# AnalogValuePreparation.net
KiCad netlist of a schematic drawn in Altium Designer
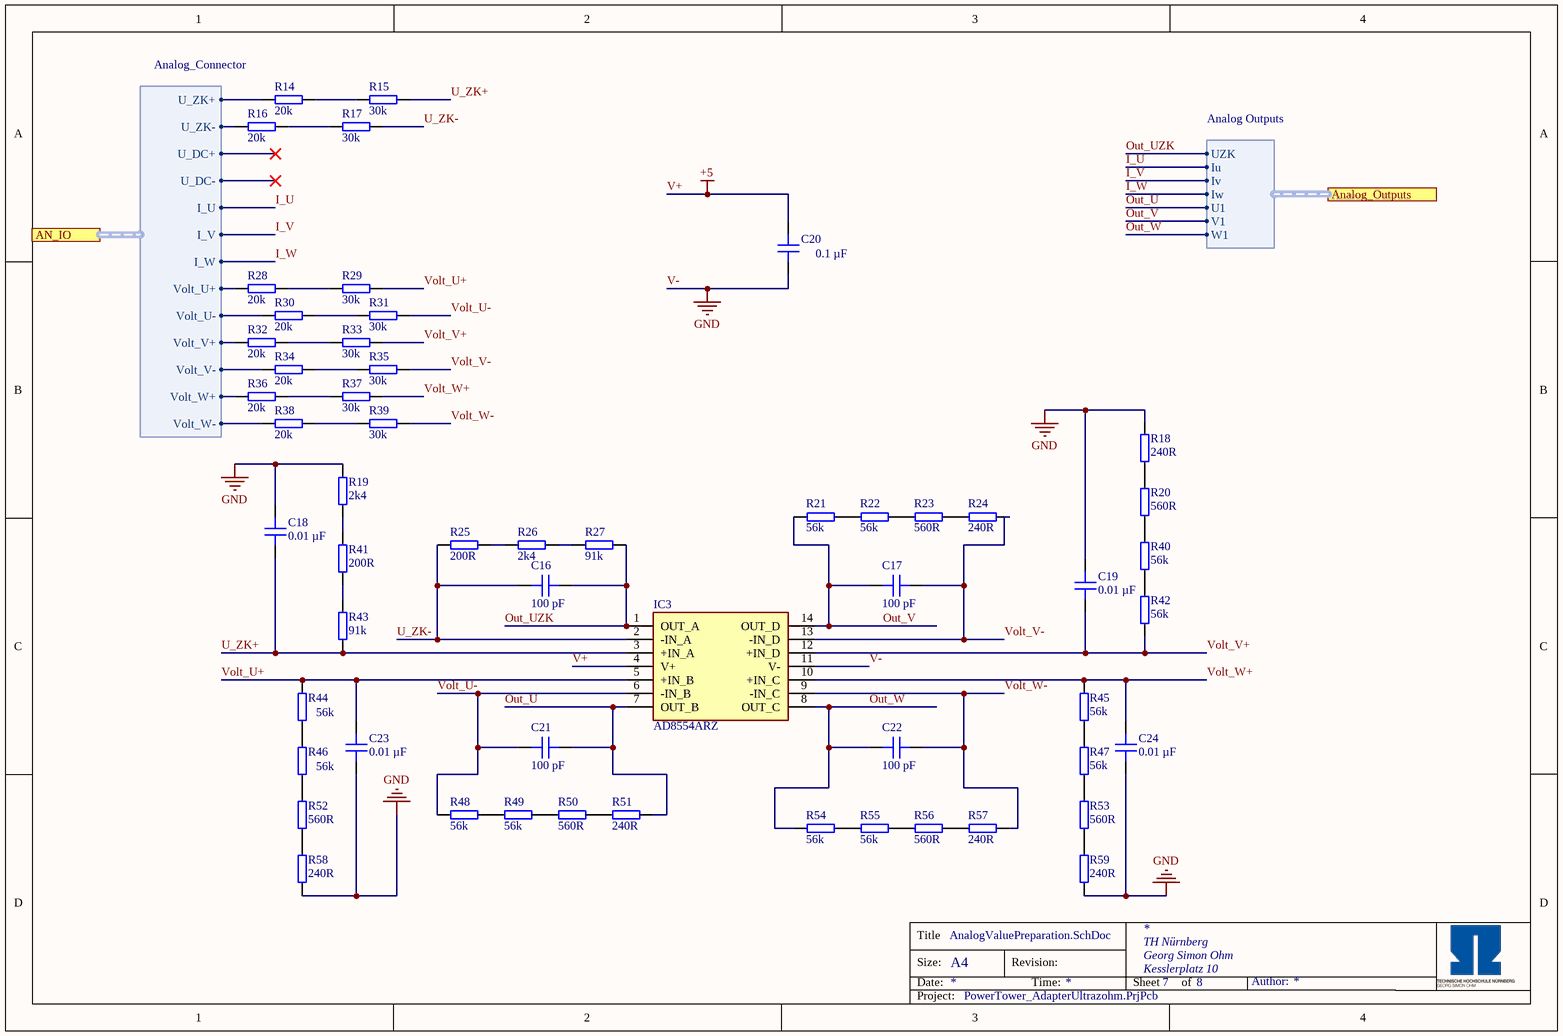
[diagram p0: AnalogValuePreparation.SchDoc]

(export (version "E")
  (design (tool "Eeschema 10.0.6"))
  (components
    (comp (ref "C16")
      (value "100 pF")
      (footprint "C_0603")
      (description "Capacitor 0603, 50 VDC, 100 pF, C0G")
      (fields
        (field (name "MANUFACTURER PART NUMBER") "885012006057")
        (field (name "MANUFACTURER") "Wuerth Elektronik")
        (field (name "CREATED FROM") "MGremer")
      )
      (libsource (lib "user") (part "Capacitor"))
    )
    (comp (ref "C17")
      (value "100 pF")
      (footprint "C_0603")
      (description "Capacitor 0603, 50 VDC, 100 pF, C0G")
      (fields
        (field (name "MANUFACTURER PART NUMBER") "885012006057")
        (field (name "MANUFACTURER") "Wuerth Elektronik")
        (field (name "CREATED FROM") "MGremer")
      )
      (libsource (lib "user") (part "Capacitor"))
    )
    (comp (ref "C18")
      (value "0.01 µF")
      (footprint "C_0603")
      (description "Capacitor 0603, 50 VDC, 0.01 µF, X7R")
      (fields
        (field (name "MANUFACTURER PART NUMBER") "GCJ188R71H103KA01D")
        (field (name "MANUFACTURER") "muRata")
        (field (name "CREATED FROM") "MGremer")
      )
      (libsource (lib "user") (part "Capacitor"))
    )
    (comp (ref "C19")
      (value "0.01 µF")
      (footprint "C_0603")
      (description "Capacitor 0603, 50 VDC, 0.01 µF, X7R")
      (fields
        (field (name "MANUFACTURER PART NUMBER") "GCJ188R71H103KA01D")
        (field (name "MANUFACTURER") "muRata")
        (field (name "CREATED FROM") "MGremer")
      )
      (libsource (lib "user") (part "Capacitor"))
    )
    (comp (ref "C20")
      (value "0.1 µF")
      (footprint "C_0603")
      (description "Capacitor 0603, 50 VDC, 0.1 µF, X7R")
      (fields
        (field (name "MANUFACTURER PART NUMBER") "C0603X104K5RAC7411")
        (field (name "MANUFACTURER") "KEMET")
        (field (name "CREATED FROM") "MGremer")
      )
      (libsource (lib "user") (part "Capacitor"))
    )
    (comp (ref "C21")
      (value "100 pF")
      (footprint "C_0603")
      (description "Capacitor 0603, 50 VDC, 100 pF, C0G")
      (fields
        (field (name "MANUFACTURER PART NUMBER") "885012006057")
        (field (name "MANUFACTURER") "Wuerth Elektronik")
        (field (name "CREATED FROM") "MGremer")
      )
      (libsource (lib "user") (part "Capacitor"))
    )
    (comp (ref "C22")
      (value "100 pF")
      (footprint "C_0603")
      (description "Capacitor 0603, 50 VDC, 100 pF, C0G")
      (fields
        (field (name "MANUFACTURER PART NUMBER") "885012006057")
        (field (name "MANUFACTURER") "Wuerth Elektronik")
        (field (name "CREATED FROM") "MGremer")
      )
      (libsource (lib "user") (part "Capacitor"))
    )
    (comp (ref "C23")
      (value "0.01 µF")
      (footprint "C_0603")
      (description "Capacitor 0603, 50 VDC, 0.01 µF, X7R")
      (fields
        (field (name "MANUFACTURER PART NUMBER") "GCJ188R71H103KA01D")
        (field (name "MANUFACTURER") "muRata")
        (field (name "CREATED FROM") "MGremer")
      )
      (libsource (lib "user") (part "Capacitor"))
    )
    (comp (ref "C24")
      (value "0.01 µF")
      (footprint "C_0603")
      (description "Capacitor 0603, 50 VDC, 0.01 µF, X7R")
      (fields
        (field (name "MANUFACTURER PART NUMBER") "GCJ188R71H103KA01D")
        (field (name "MANUFACTURER") "muRata")
        (field (name "CREATED FROM") "MGremer")
      )
      (libsource (lib "user") (part "Capacitor"))
    )
    (comp (ref "IC3")
      (value "AD8554ARZ")
      (footprint "SOIC127P600X175-14N")
      (description "Differential Amplifier, 3V 1.5MHz, 145dB")
      (fields (field (name "MANUFACTURER") "Analog Devices") (field (name "CREATED FROM") "TWilfling"))
      (libsource (lib "user") (part "AD8554ARZ"))
    )
    (comp (ref "R14")
      (value "20k")
      (footprint "RES 0603_1608")
      (description "SMD resistor E24 series")
      (fields
        (field (name "MANUFACTURER PART NUMBER") "RK73B1JTTD203J")
        (field (name "MANUFACTURER") "KOA Speer")
        (field (name "CREATED FROM") "MGremer")
      )
      (libsource (lib "user") (part "Resistor"))
    )
    (comp (ref "R15")
      (value "30k")
      (footprint "RES 0603_1608")
      (description "SMD resistor E24 series")
      (fields
        (field (name "MANUFACTURER PART NUMBER") "RK73B1JTTD303J")
        (field (name "MANUFACTURER") "KOA Speer")
        (field (name "CREATED FROM") "MGremer")
      )
      (libsource (lib "user") (part "Resistor"))
    )
    (comp (ref "R16")
      (value "20k")
      (footprint "RES 0603_1608")
      (description "SMD resistor E24 series")
      (fields
        (field (name "MANUFACTURER PART NUMBER") "RK73B1JTTD203J")
        (field (name "MANUFACTURER") "KOA Speer")
        (field (name "CREATED FROM") "MGremer")
      )
      (libsource (lib "user") (part "Resistor"))
    )
    (comp (ref "R17")
      (value "30k")
      (footprint "RES 0603_1608")
      (description "SMD resistor E24 series")
      (fields
        (field (name "MANUFACTURER PART NUMBER") "RK73B1JTTD303J")
        (field (name "MANUFACTURER") "KOA Speer")
        (field (name "CREATED FROM") "MGremer")
      )
      (libsource (lib "user") (part "Resistor"))
    )
    (comp (ref "R18")
      (value "240R")
      (footprint "RES 0603_1608")
      (description "SMD resistor E24 series")
      (fields
        (field (name "MANUFACTURER PART NUMBER") "RK73B1JTTDD241J")
        (field (name "MANUFACTURER") "KOA Speer")
        (field (name "CREATED FROM") "MGremer")
      )
      (libsource (lib "user") (part "Resistor"))
    )
    (comp (ref "R19")
      (value "2k4")
      (footprint "RES 0603_1608")
      (description "SMD resistor E24 series")
      (fields
        (field (name "MANUFACTURER PART NUMBER") "RK73B1JTTDD242J")
        (field (name "MANUFACTURER") "KOA Speer")
        (field (name "CREATED FROM") "MGremer")
      )
      (libsource (lib "user") (part "Resistor"))
    )
    (comp (ref "R20")
      (value "560R")
      (footprint "RES 0603_1608")
      (description "SMD resistor E24 series")
      (fields
        (field (name "MANUFACTURER PART NUMBER") "RK73B1JTTD561J")
        (field (name "MANUFACTURER") "KOA Speer")
        (field (name "CREATED FROM") "MGremer")
      )
      (libsource (lib "user") (part "Resistor"))
    )
    (comp (ref "R21")
      (value "56k")
      (footprint "RES 0603_1608")
      (description "SMD resistor E24 series")
      (fields
        (field (name "MANUFACTURER PART NUMBER") "RK73B1JTTDD563J")
        (field (name "MANUFACTURER") "KOA Speer")
        (field (name "CREATED FROM") "MGremer")
      )
      (libsource (lib "user") (part "Resistor"))
    )
    (comp (ref "R22")
      (value "56k")
      (footprint "RES 0603_1608")
      (description "SMD resistor E24 series")
      (fields
        (field (name "MANUFACTURER PART NUMBER") "RK73B1JTTDD563J")
        (field (name "MANUFACTURER") "KOA Speer")
        (field (name "CREATED FROM") "MGremer")
      )
      (libsource (lib "user") (part "Resistor"))
    )
    (comp (ref "R23")
      (value "560R")
      (footprint "RES 0603_1608")
      (description "SMD resistor E24 series")
      (fields
        (field (name "MANUFACTURER PART NUMBER") "RK73B1JTTD561J")
        (field (name "MANUFACTURER") "KOA Speer")
        (field (name "CREATED FROM") "MGremer")
      )
      (libsource (lib "user") (part "Resistor"))
    )
    (comp (ref "R24")
      (value "240R")
      (footprint "RES 0603_1608")
      (description "SMD resistor E24 series")
      (fields
        (field (name "MANUFACTURER PART NUMBER") "RK73B1JTTDD241J")
        (field (name "MANUFACTURER") "KOA Speer")
        (field (name "CREATED FROM") "MGremer")
      )
      (libsource (lib "user") (part "Resistor"))
    )
    (comp (ref "R25")
      (value "200R")
      (footprint "RES 0603_1608")
      (description "SMD resistor E24 series")
      (fields
        (field (name "MANUFACTURER PART NUMBER") "RK73B1JTTD201J")
        (field (name "MANUFACTURER") "KOA Speer")
        (field (name "CREATED FROM") "MGremer")
      )
      (libsource (lib "user") (part "Resistor"))
    )
    (comp (ref "R26")
      (value "2k4")
      (footprint "RES 0603_1608")
      (description "SMD resistor E24 series")
      (fields
        (field (name "MANUFACTURER PART NUMBER") "RK73B1JTTDD242J")
        (field (name "MANUFACTURER") "KOA Speer")
        (field (name "CREATED FROM") "MGremer")
      )
      (libsource (lib "user") (part "Resistor"))
    )
    (comp (ref "R27")
      (value "91k")
      (footprint "RES 0603_1608")
      (description "SMD resistor E24 series")
      (fields
        (field (name "MANUFACTURER PART NUMBER") "RK73B1JTTDD913J")
        (field (name "MANUFACTURER") "KOA Speer")
        (field (name "CREATED FROM") "MGremer")
      )
      (libsource (lib "user") (part "Resistor"))
    )
    (comp (ref "R28")
      (value "20k")
      (footprint "RES 0603_1608")
      (description "SMD resistor E24 series")
      (fields
        (field (name "MANUFACTURER PART NUMBER") "RK73B1JTTD203J")
        (field (name "MANUFACTURER") "KOA Speer")
        (field (name "CREATED FROM") "MGremer")
      )
      (libsource (lib "user") (part "Resistor"))
    )
    (comp (ref "R29")
      (value "30k")
      (footprint "RES 0603_1608")
      (description "SMD resistor E24 series")
      (fields
        (field (name "MANUFACTURER PART NUMBER") "RK73B1JTTD303J")
        (field (name "MANUFACTURER") "KOA Speer")
        (field (name "CREATED FROM") "MGremer")
      )
      (libsource (lib "user") (part "Resistor"))
    )
    (comp (ref "R30")
      (value "20k")
      (footprint "RES 0603_1608")
      (description "SMD resistor E24 series")
      (fields
        (field (name "MANUFACTURER PART NUMBER") "RK73B1JTTD203J")
        (field (name "MANUFACTURER") "KOA Speer")
        (field (name "CREATED FROM") "MGremer")
      )
      (libsource (lib "user") (part "Resistor"))
    )
    (comp (ref "R31")
      (value "30k")
      (footprint "RES 0603_1608")
      (description "SMD resistor E24 series")
      (fields
        (field (name "MANUFACTURER PART NUMBER") "RK73B1JTTD303J")
        (field (name "MANUFACTURER") "KOA Speer")
        (field (name "CREATED FROM") "MGremer")
      )
      (libsource (lib "user") (part "Resistor"))
    )
    (comp (ref "R32")
      (value "20k")
      (footprint "RES 0603_1608")
      (description "SMD resistor E24 series")
      (fields
        (field (name "MANUFACTURER PART NUMBER") "RK73B1JTTD203J")
        (field (name "MANUFACTURER") "KOA Speer")
        (field (name "CREATED FROM") "MGremer")
      )
      (libsource (lib "user") (part "Resistor"))
    )
    (comp (ref "R33")
      (value "30k")
      (footprint "RES 0603_1608")
      (description "SMD resistor E24 series")
      (fields
        (field (name "MANUFACTURER PART NUMBER") "RK73B1JTTD303J")
        (field (name "MANUFACTURER") "KOA Speer")
        (field (name "CREATED FROM") "MGremer")
      )
      (libsource (lib "user") (part "Resistor"))
    )
    (comp (ref "R34")
      (value "20k")
      (footprint "RES 0603_1608")
      (description "SMD resistor E24 series")
      (fields
        (field (name "MANUFACTURER PART NUMBER") "RK73B1JTTD203J")
        (field (name "MANUFACTURER") "KOA Speer")
        (field (name "CREATED FROM") "MGremer")
      )
      (libsource (lib "user") (part "Resistor"))
    )
    (comp (ref "R35")
      (value "30k")
      (footprint "RES 0603_1608")
      (description "SMD resistor E24 series")
      (fields
        (field (name "MANUFACTURER PART NUMBER") "RK73B1JTTD303J")
        (field (name "MANUFACTURER") "KOA Speer")
        (field (name "CREATED FROM") "MGremer")
      )
      (libsource (lib "user") (part "Resistor"))
    )
    (comp (ref "R36")
      (value "20k")
      (footprint "RES 0603_1608")
      (description "SMD resistor E24 series")
      (fields
        (field (name "MANUFACTURER PART NUMBER") "RK73B1JTTD203J")
        (field (name "MANUFACTURER") "KOA Speer")
        (field (name "CREATED FROM") "MGremer")
      )
      (libsource (lib "user") (part "Resistor"))
    )
    (comp (ref "R37")
      (value "30k")
      (footprint "RES 0603_1608")
      (description "SMD resistor E24 series")
      (fields
        (field (name "MANUFACTURER PART NUMBER") "RK73B1JTTD303J")
        (field (name "MANUFACTURER") "KOA Speer")
        (field (name "CREATED FROM") "MGremer")
      )
      (libsource (lib "user") (part "Resistor"))
    )
    (comp (ref "R38")
      (value "20k")
      (footprint "RES 0603_1608")
      (description "SMD resistor E24 series")
      (fields
        (field (name "MANUFACTURER PART NUMBER") "RK73B1JTTD203J")
        (field (name "MANUFACTURER") "KOA Speer")
        (field (name "CREATED FROM") "MGremer")
      )
      (libsource (lib "user") (part "Resistor"))
    )
    (comp (ref "R39")
      (value "30k")
      (footprint "RES 0603_1608")
      (description "SMD resistor E24 series")
      (fields
        (field (name "MANUFACTURER PART NUMBER") "RK73B1JTTD303J")
        (field (name "MANUFACTURER") "KOA Speer")
        (field (name "CREATED FROM") "MGremer")
      )
      (libsource (lib "user") (part "Resistor"))
    )
    (comp (ref "R40")
      (value "56k")
      (footprint "RES 0603_1608")
      (description "SMD resistor E24 series")
      (fields
        (field (name "MANUFACTURER PART NUMBER") "RK73B1JTTDD563J")
        (field (name "MANUFACTURER") "KOA Speer")
        (field (name "CREATED FROM") "MGremer")
      )
      (libsource (lib "user") (part "Resistor"))
    )
    (comp (ref "R41")
      (value "200R")
      (footprint "RES 0603_1608")
      (description "SMD resistor E24 series")
      (fields
        (field (name "MANUFACTURER PART NUMBER") "RK73B1JTTD201J")
        (field (name "MANUFACTURER") "KOA Speer")
        (field (name "CREATED FROM") "MGremer")
      )
      (libsource (lib "user") (part "Resistor"))
    )
    (comp (ref "R42")
      (value "56k")
      (footprint "RES 0603_1608")
      (description "SMD resistor E24 series")
      (fields
        (field (name "MANUFACTURER PART NUMBER") "RK73B1JTTDD563J")
        (field (name "MANUFACTURER") "KOA Speer")
        (field (name "CREATED FROM") "MGremer")
      )
      (libsource (lib "user") (part "Resistor"))
    )
    (comp (ref "R43")
      (value "91k")
      (footprint "RES 0603_1608")
      (description "SMD resistor E24 series")
      (fields
        (field (name "MANUFACTURER PART NUMBER") "RK73B1JTTDD913J")
        (field (name "MANUFACTURER") "KOA Speer")
        (field (name "CREATED FROM") "MGremer")
      )
      (libsource (lib "user") (part "Resistor"))
    )
    (comp (ref "R44")
      (value "56k")
      (footprint "RES 0603_1608")
      (description "SMD resistor E24 series")
      (fields
        (field (name "MANUFACTURER PART NUMBER") "RK73B1JTTDD563J")
        (field (name "MANUFACTURER") "KOA Speer")
        (field (name "CREATED FROM") "MGremer")
      )
      (libsource (lib "user") (part "Resistor"))
    )
    (comp (ref "R45")
      (value "56k")
      (footprint "RES 0603_1608")
      (description "SMD resistor E24 series")
      (fields
        (field (name "MANUFACTURER PART NUMBER") "RK73B1JTTDD563J")
        (field (name "MANUFACTURER") "KOA Speer")
        (field (name "CREATED FROM") "MGremer")
      )
      (libsource (lib "user") (part "Resistor"))
    )
    (comp (ref "R46")
      (value "56k")
      (footprint "RES 0603_1608")
      (description "SMD resistor E24 series")
      (fields
        (field (name "MANUFACTURER PART NUMBER") "RK73B1JTTDD563J")
        (field (name "MANUFACTURER") "KOA Speer")
        (field (name "CREATED FROM") "MGremer")
      )
      (libsource (lib "user") (part "Resistor"))
    )
    (comp (ref "R47")
      (value "56k")
      (footprint "RES 0603_1608")
      (description "SMD resistor E24 series")
      (fields
        (field (name "MANUFACTURER PART NUMBER") "RK73B1JTTDD563J")
        (field (name "MANUFACTURER") "KOA Speer")
        (field (name "CREATED FROM") "MGremer")
      )
      (libsource (lib "user") (part "Resistor"))
    )
    (comp (ref "R48")
      (value "56k")
      (footprint "RES 0603_1608")
      (description "SMD resistor E24 series")
      (fields
        (field (name "MANUFACTURER PART NUMBER") "RK73B1JTTDD563J")
        (field (name "MANUFACTURER") "KOA Speer")
        (field (name "CREATED FROM") "MGremer")
      )
      (libsource (lib "user") (part "Resistor"))
    )
    (comp (ref "R49")
      (value "56k")
      (footprint "RES 0603_1608")
      (description "SMD resistor E24 series")
      (fields
        (field (name "MANUFACTURER PART NUMBER") "RK73B1JTTDD563J")
        (field (name "MANUFACTURER") "KOA Speer")
        (field (name "CREATED FROM") "MGremer")
      )
      (libsource (lib "user") (part "Resistor"))
    )
    (comp (ref "R50")
      (value "560R")
      (footprint "RES 0603_1608")
      (description "SMD resistor E24 series")
      (fields
        (field (name "MANUFACTURER PART NUMBER") "RK73B1JTTD561J")
        (field (name "MANUFACTURER") "KOA Speer")
        (field (name "CREATED FROM") "MGremer")
      )
      (libsource (lib "user") (part "Resistor"))
    )
    (comp (ref "R51")
      (value "240R")
      (footprint "RES 0603_1608")
      (description "SMD resistor E24 series")
      (fields
        (field (name "MANUFACTURER PART NUMBER") "RK73B1JTTDD241J")
        (field (name "MANUFACTURER") "KOA Speer")
        (field (name "CREATED FROM") "MGremer")
      )
      (libsource (lib "user") (part "Resistor"))
    )
    (comp (ref "R52")
      (value "560R")
      (footprint "RES 0603_1608")
      (description "SMD resistor E24 series")
      (fields
        (field (name "MANUFACTURER PART NUMBER") "RK73B1JTTD561J")
        (field (name "MANUFACTURER") "KOA Speer")
        (field (name "CREATED FROM") "MGremer")
      )
      (libsource (lib "user") (part "Resistor"))
    )
    (comp (ref "R53")
      (value "560R")
      (footprint "RES 0603_1608")
      (description "SMD resistor E24 series")
      (fields
        (field (name "MANUFACTURER PART NUMBER") "RK73B1JTTD561J")
        (field (name "MANUFACTURER") "KOA Speer")
        (field (name "CREATED FROM") "MGremer")
      )
      (libsource (lib "user") (part "Resistor"))
    )
    (comp (ref "R54")
      (value "56k")
      (footprint "RES 0603_1608")
      (description "SMD resistor E24 series")
      (fields
        (field (name "MANUFACTURER PART NUMBER") "RK73B1JTTDD563J")
        (field (name "MANUFACTURER") "KOA Speer")
        (field (name "CREATED FROM") "MGremer")
      )
      (libsource (lib "user") (part "Resistor"))
    )
    (comp (ref "R55")
      (value "56k")
      (footprint "RES 0603_1608")
      (description "SMD resistor E24 series")
      (fields
        (field (name "MANUFACTURER PART NUMBER") "RK73B1JTTDD563J")
        (field (name "MANUFACTURER") "KOA Speer")
        (field (name "CREATED FROM") "MGremer")
      )
      (libsource (lib "user") (part "Resistor"))
    )
    (comp (ref "R56")
      (value "560R")
      (footprint "RES 0603_1608")
      (description "SMD resistor E24 series")
      (fields
        (field (name "MANUFACTURER PART NUMBER") "RK73B1JTTD561J")
        (field (name "MANUFACTURER") "KOA Speer")
        (field (name "CREATED FROM") "MGremer")
      )
      (libsource (lib "user") (part "Resistor"))
    )
    (comp (ref "R57")
      (value "240R")
      (footprint "RES 0603_1608")
      (description "SMD resistor E24 series")
      (fields
        (field (name "MANUFACTURER PART NUMBER") "RK73B1JTTDD241J")
        (field (name "MANUFACTURER") "KOA Speer")
        (field (name "CREATED FROM") "MGremer")
      )
      (libsource (lib "user") (part "Resistor"))
    )
    (comp (ref "R58")
      (value "240R")
      (footprint "RES 0603_1608")
      (description "SMD resistor E24 series")
      (fields
        (field (name "MANUFACTURER PART NUMBER") "RK73B1JTTDD241J")
        (field (name "MANUFACTURER") "KOA Speer")
        (field (name "CREATED FROM") "MGremer")
      )
      (libsource (lib "user") (part "Resistor"))
    )
    (comp (ref "R59")
      (value "240R")
      (footprint "RES 0603_1608")
      (description "SMD resistor E24 series")
      (fields
        (field (name "MANUFACTURER PART NUMBER") "RK73B1JTTDD241J")
        (field (name "MANUFACTURER") "KOA Speer")
        (field (name "CREATED FROM") "MGremer")
      )
      (libsource (lib "user") (part "Resistor"))
    )
  )
  (nets
    (net (code "4") (name "+5") (class "Default")
      (node (ref "C20") (pin "2") (pinfunction "2_2") (pintype "passive"))
      (node (ref "IC3") (pin "4") (pinfunction "V+_4") (pintype "passive"))
    )
    (net (code "8") (name "/Out_U") (class "Default")
      (node (ref "C21") (pin "1") (pinfunction "1_1") (pintype "passive"))
      (node (ref "IC3") (pin "7") (pinfunction "OUT_B_7") (pintype "passive"))
      (node (ref "R51") (pin "2") (pinfunction "2_2") (pintype "passive"))
    )
    (net (code "9") (name "/Out_UZK") (class "Default")
      (node (ref "C16") (pin "2") (pinfunction "2_2") (pintype "passive"))
      (node (ref "IC3") (pin "1") (pinfunction "OUT_A_1") (pintype "passive"))
      (node (ref "R27") (pin "2") (pinfunction "2_2") (pintype "passive"))
    )
    (net (code "10") (name "/Out_V") (class "Default")
      (node (ref "C17") (pin "1") (pinfunction "1_1") (pintype "passive"))
      (node (ref "IC3") (pin "14") (pinfunction "OUT_D_14") (pintype "passive"))
      (node (ref "R21") (pin "1") (pinfunction "1_1") (pintype "passive"))
    )
    (net (code "11") (name "/Out_W") (class "Default")
      (node (ref "C22") (pin "2") (pinfunction "2_2") (pintype "passive"))
      (node (ref "IC3") (pin "8") (pinfunction "OUT_C_8") (pintype "passive"))
      (node (ref "R54") (pin "1") (pinfunction "1_1") (pintype "passive"))
    )
    (net (code "12") (name "/U_ZK+") (class "Default")
      (node (ref "C18") (pin "1") (pinfunction "1_1") (pintype "passive"))
      (node (ref "IC3") (pin "3") (pinfunction "+IN_A_3") (pintype "passive"))
      (node (ref "R15") (pin "2") (pinfunction "2_2") (pintype "passive"))
      (node (ref "R43") (pin "1") (pinfunction "1_1") (pintype "passive"))
    )
    (net (code "13") (name "/U_ZK-") (class "Default")
      (node (ref "C16") (pin "1") (pinfunction "1_1") (pintype "passive"))
      (node (ref "IC3") (pin "2") (pinfunction "-IN_A_2") (pintype "passive"))
      (node (ref "R17") (pin "2") (pinfunction "2_2") (pintype "passive"))
      (node (ref "R25") (pin "1") (pinfunction "1_1") (pintype "passive"))
    )
    (net (code "14") (name "/Volt_U+") (class "Default")
      (node (ref "C23") (pin "1") (pinfunction "1_1") (pintype "passive"))
      (node (ref "IC3") (pin "5") (pinfunction "+IN_B_5") (pintype "passive"))
      (node (ref "R29") (pin "2") (pinfunction "2_2") (pintype "passive"))
      (node (ref "R44") (pin "1") (pinfunction "1_1") (pintype "passive"))
    )
    (net (code "15") (name "/Volt_U-") (class "Default")
      (node (ref "C21") (pin "2") (pinfunction "2_2") (pintype "passive"))
      (node (ref "IC3") (pin "6") (pinfunction "-IN_B_6") (pintype "passive"))
      (node (ref "R31") (pin "2") (pinfunction "2_2") (pintype "passive"))
      (node (ref "R48") (pin "1") (pinfunction "1_1") (pintype "passive"))
    )
    (net (code "16") (name "/Volt_V+") (class "Default")
      (node (ref "C19") (pin "1") (pinfunction "1_1") (pintype "passive"))
      (node (ref "IC3") (pin "12") (pinfunction "+IN_D_12") (pintype "passive"))
      (node (ref "R33") (pin "2") (pinfunction "2_2") (pintype "passive"))
      (node (ref "R42") (pin "1") (pinfunction "1_1") (pintype "passive"))
    )
    (net (code "17") (name "/Volt_V-") (class "Default")
      (node (ref "C17") (pin "2") (pinfunction "2_2") (pintype "passive"))
      (node (ref "IC3") (pin "13") (pinfunction "-IN_D_13") (pintype "passive"))
      (node (ref "R24") (pin "2") (pinfunction "2_2") (pintype "passive"))
      (node (ref "R35") (pin "2") (pinfunction "2_2") (pintype "passive"))
    )
    (net (code "18") (name "/Volt_W+") (class "Default")
      (node (ref "C24") (pin "1") (pinfunction "1_1") (pintype "passive"))
      (node (ref "IC3") (pin "10") (pinfunction "+IN_C_10") (pintype "passive"))
      (node (ref "R37") (pin "2") (pinfunction "2_2") (pintype "passive"))
      (node (ref "R45") (pin "1") (pinfunction "1_1") (pintype "passive"))
    )
    (net (code "19") (name "/Volt_W-") (class "Default")
      (node (ref "C22") (pin "1") (pinfunction "1_1") (pintype "passive"))
      (node (ref "IC3") (pin "9") (pinfunction "-IN_C_9") (pintype "passive"))
      (node (ref "R39") (pin "2") (pinfunction "2_2") (pintype "passive"))
      (node (ref "R57") (pin "2") (pinfunction "2_2") (pintype "passive"))
    )
    (net (code "22") (name "GND") (class "Default")
      (node (ref "C18") (pin "2") (pinfunction "2_2") (pintype "passive"))
      (node (ref "C19") (pin "2") (pinfunction "2_2") (pintype "passive"))
      (node (ref "C20") (pin "1") (pinfunction "1_1") (pintype "passive"))
      (node (ref "C23") (pin "2") (pinfunction "2_2") (pintype "passive"))
      (node (ref "C24") (pin "2") (pinfunction "2_2") (pintype "passive"))
      (node (ref "IC3") (pin "11") (pinfunction "V-_11") (pintype "passive"))
      (node (ref "R18") (pin "2") (pinfunction "2_2") (pintype "passive"))
      (node (ref "R19") (pin "2") (pinfunction "2_2") (pintype "passive"))
      (node (ref "R58") (pin "2") (pinfunction "2_2") (pintype "passive"))
      (node (ref "R59") (pin "2") (pinfunction "2_2") (pintype "passive"))
    )
    (net (code "23") (name "Net-(R14-Pad2)") (class "Default")
      (node (ref "R14") (pin "2") (pinfunction "2_2") (pintype "passive"))
      (node (ref "R15") (pin "1") (pinfunction "1_1") (pintype "passive"))
    )
    (net (code "24") (name "Net-(R16-Pad2)") (class "Default")
      (node (ref "R16") (pin "2") (pinfunction "2_2") (pintype "passive"))
      (node (ref "R17") (pin "1") (pinfunction "1_1") (pintype "passive"))
    )
    (net (code "25") (name "Net-(R18-Pad1)") (class "Default")
      (node (ref "R18") (pin "1") (pinfunction "1_1") (pintype "passive"))
      (node (ref "R20") (pin "2") (pinfunction "2_2") (pintype "passive"))
    )
    (net (code "26") (name "Net-(R19-Pad1)") (class "Default")
      (node (ref "R19") (pin "1") (pinfunction "1_1") (pintype "passive"))
      (node (ref "R41") (pin "2") (pinfunction "2_2") (pintype "passive"))
    )
    (net (code "27") (name "Net-(R20-Pad1)") (class "Default")
      (node (ref "R20") (pin "1") (pinfunction "1_1") (pintype "passive"))
      (node (ref "R40") (pin "2") (pinfunction "2_2") (pintype "passive"))
    )
    (net (code "28") (name "Net-(R21-Pad2)") (class "Default")
      (node (ref "R21") (pin "2") (pinfunction "2_2") (pintype "passive"))
      (node (ref "R22") (pin "1") (pinfunction "1_1") (pintype "passive"))
    )
    (net (code "29") (name "Net-(R22-Pad2)") (class "Default")
      (node (ref "R22") (pin "2") (pinfunction "2_2") (pintype "passive"))
      (node (ref "R23") (pin "1") (pinfunction "1_1") (pintype "passive"))
    )
    (net (code "30") (name "Net-(R23-Pad2)") (class "Default")
      (node (ref "R23") (pin "2") (pinfunction "2_2") (pintype "passive"))
      (node (ref "R24") (pin "1") (pinfunction "1_1") (pintype "passive"))
    )
    (net (code "31") (name "Net-(R25-Pad2)") (class "Default")
      (node (ref "R25") (pin "2") (pinfunction "2_2") (pintype "passive"))
      (node (ref "R26") (pin "1") (pinfunction "1_1") (pintype "passive"))
    )
    (net (code "32") (name "Net-(R26-Pad2)") (class "Default")
      (node (ref "R26") (pin "2") (pinfunction "2_2") (pintype "passive"))
      (node (ref "R27") (pin "1") (pinfunction "1_1") (pintype "passive"))
    )
    (net (code "33") (name "Net-(R28-Pad2)") (class "Default")
      (node (ref "R28") (pin "2") (pinfunction "2_2") (pintype "passive"))
      (node (ref "R29") (pin "1") (pinfunction "1_1") (pintype "passive"))
    )
    (net (code "34") (name "Net-(R30-Pad2)") (class "Default")
      (node (ref "R30") (pin "2") (pinfunction "2_2") (pintype "passive"))
      (node (ref "R31") (pin "1") (pinfunction "1_1") (pintype "passive"))
    )
    (net (code "35") (name "Net-(R32-Pad2)") (class "Default")
      (node (ref "R32") (pin "2") (pinfunction "2_2") (pintype "passive"))
      (node (ref "R33") (pin "1") (pinfunction "1_1") (pintype "passive"))
    )
    (net (code "36") (name "Net-(R34-Pad2)") (class "Default")
      (node (ref "R34") (pin "2") (pinfunction "2_2") (pintype "passive"))
      (node (ref "R35") (pin "1") (pinfunction "1_1") (pintype "passive"))
    )
    (net (code "37") (name "Net-(R36-Pad2)") (class "Default")
      (node (ref "R36") (pin "2") (pinfunction "2_2") (pintype "passive"))
      (node (ref "R37") (pin "1") (pinfunction "1_1") (pintype "passive"))
    )
    (net (code "38") (name "Net-(R38-Pad2)") (class "Default")
      (node (ref "R38") (pin "2") (pinfunction "2_2") (pintype "passive"))
      (node (ref "R39") (pin "1") (pinfunction "1_1") (pintype "passive"))
    )
    (net (code "39") (name "Net-(R40-Pad1)") (class "Default")
      (node (ref "R40") (pin "1") (pinfunction "1_1") (pintype "passive"))
      (node (ref "R42") (pin "2") (pinfunction "2_2") (pintype "passive"))
    )
    (net (code "40") (name "Net-(R41-Pad1)") (class "Default")
      (node (ref "R41") (pin "1") (pinfunction "1_1") (pintype "passive"))
      (node (ref "R43") (pin "2") (pinfunction "2_2") (pintype "passive"))
    )
    (net (code "41") (name "Net-(R44-Pad2)") (class "Default")
      (node (ref "R44") (pin "2") (pinfunction "2_2") (pintype "passive"))
      (node (ref "R46") (pin "1") (pinfunction "1_1") (pintype "passive"))
    )
    (net (code "42") (name "Net-(R45-Pad2)") (class "Default")
      (node (ref "R45") (pin "2") (pinfunction "2_2") (pintype "passive"))
      (node (ref "R47") (pin "1") (pinfunction "1_1") (pintype "passive"))
    )
    (net (code "43") (name "Net-(R46-Pad2)") (class "Default")
      (node (ref "R46") (pin "2") (pinfunction "2_2") (pintype "passive"))
      (node (ref "R52") (pin "1") (pinfunction "1_1") (pintype "passive"))
    )
    (net (code "44") (name "Net-(R47-Pad2)") (class "Default")
      (node (ref "R47") (pin "2") (pinfunction "2_2") (pintype "passive"))
      (node (ref "R53") (pin "1") (pinfunction "1_1") (pintype "passive"))
    )
    (net (code "45") (name "Net-(R48-Pad2)") (class "Default")
      (node (ref "R48") (pin "2") (pinfunction "2_2") (pintype "passive"))
      (node (ref "R49") (pin "1") (pinfunction "1_1") (pintype "passive"))
    )
    (net (code "46") (name "Net-(R49-Pad2)") (class "Default")
      (node (ref "R49") (pin "2") (pinfunction "2_2") (pintype "passive"))
      (node (ref "R50") (pin "1") (pinfunction "1_1") (pintype "passive"))
    )
    (net (code "47") (name "Net-(R50-Pad2)") (class "Default")
      (node (ref "R50") (pin "2") (pinfunction "2_2") (pintype "passive"))
      (node (ref "R51") (pin "1") (pinfunction "1_1") (pintype "passive"))
    )
    (net (code "48") (name "Net-(R52-Pad2)") (class "Default")
      (node (ref "R52") (pin "2") (pinfunction "2_2") (pintype "passive"))
      (node (ref "R58") (pin "1") (pinfunction "1_1") (pintype "passive"))
    )
    (net (code "49") (name "Net-(R53-Pad2)") (class "Default")
      (node (ref "R53") (pin "2") (pinfunction "2_2") (pintype "passive"))
      (node (ref "R59") (pin "1") (pinfunction "1_1") (pintype "passive"))
    )
    (net (code "50") (name "Net-(R54-Pad2)") (class "Default")
      (node (ref "R54") (pin "2") (pinfunction "2_2") (pintype "passive"))
      (node (ref "R55") (pin "1") (pinfunction "1_1") (pintype "passive"))
    )
    (net (code "51") (name "Net-(R55-Pad2)") (class "Default")
      (node (ref "R55") (pin "2") (pinfunction "2_2") (pintype "passive"))
      (node (ref "R56") (pin "1") (pinfunction "1_1") (pintype "passive"))
    )
    (net (code "52") (name "Net-(R56-Pad2)") (class "Default")
      (node (ref "R56") (pin "2") (pinfunction "2_2") (pintype "passive"))
      (node (ref "R57") (pin "1") (pinfunction "1_1") (pintype "passive"))
    )
    (net (code "53") (name "unconnected-(R14-Pad1)") (class "Default")
      (node (ref "R14") (pin "1") (pinfunction "1_1") (pintype "passive"))
    )
    (net (code "54") (name "unconnected-(R16-Pad1)") (class "Default")
      (node (ref "R16") (pin "1") (pinfunction "1_1") (pintype "passive"))
    )
    (net (code "55") (name "unconnected-(R28-Pad1)") (class "Default")
      (node (ref "R28") (pin "1") (pinfunction "1_1") (pintype "passive"))
    )
    (net (code "56") (name "unconnected-(R30-Pad1)") (class "Default")
      (node (ref "R30") (pin "1") (pinfunction "1_1") (pintype "passive"))
    )
    (net (code "57") (name "unconnected-(R32-Pad1)") (class "Default")
      (node (ref "R32") (pin "1") (pinfunction "1_1") (pintype "passive"))
    )
    (net (code "58") (name "unconnected-(R34-Pad1)") (class "Default")
      (node (ref "R34") (pin "1") (pinfunction "1_1") (pintype "passive"))
    )
    (net (code "59") (name "unconnected-(R36-Pad1)") (class "Default")
      (node (ref "R36") (pin "1") (pinfunction "1_1") (pintype "passive"))
    )
    (net (code "60") (name "unconnected-(R38-Pad1)") (class "Default")
      (node (ref "R38") (pin "1") (pinfunction "1_1") (pintype "passive"))
    )
  )
)
